# attiny13ReobasNew_2021-02-27.net
KiCad netlist of a schematic drawn in EasyEDA
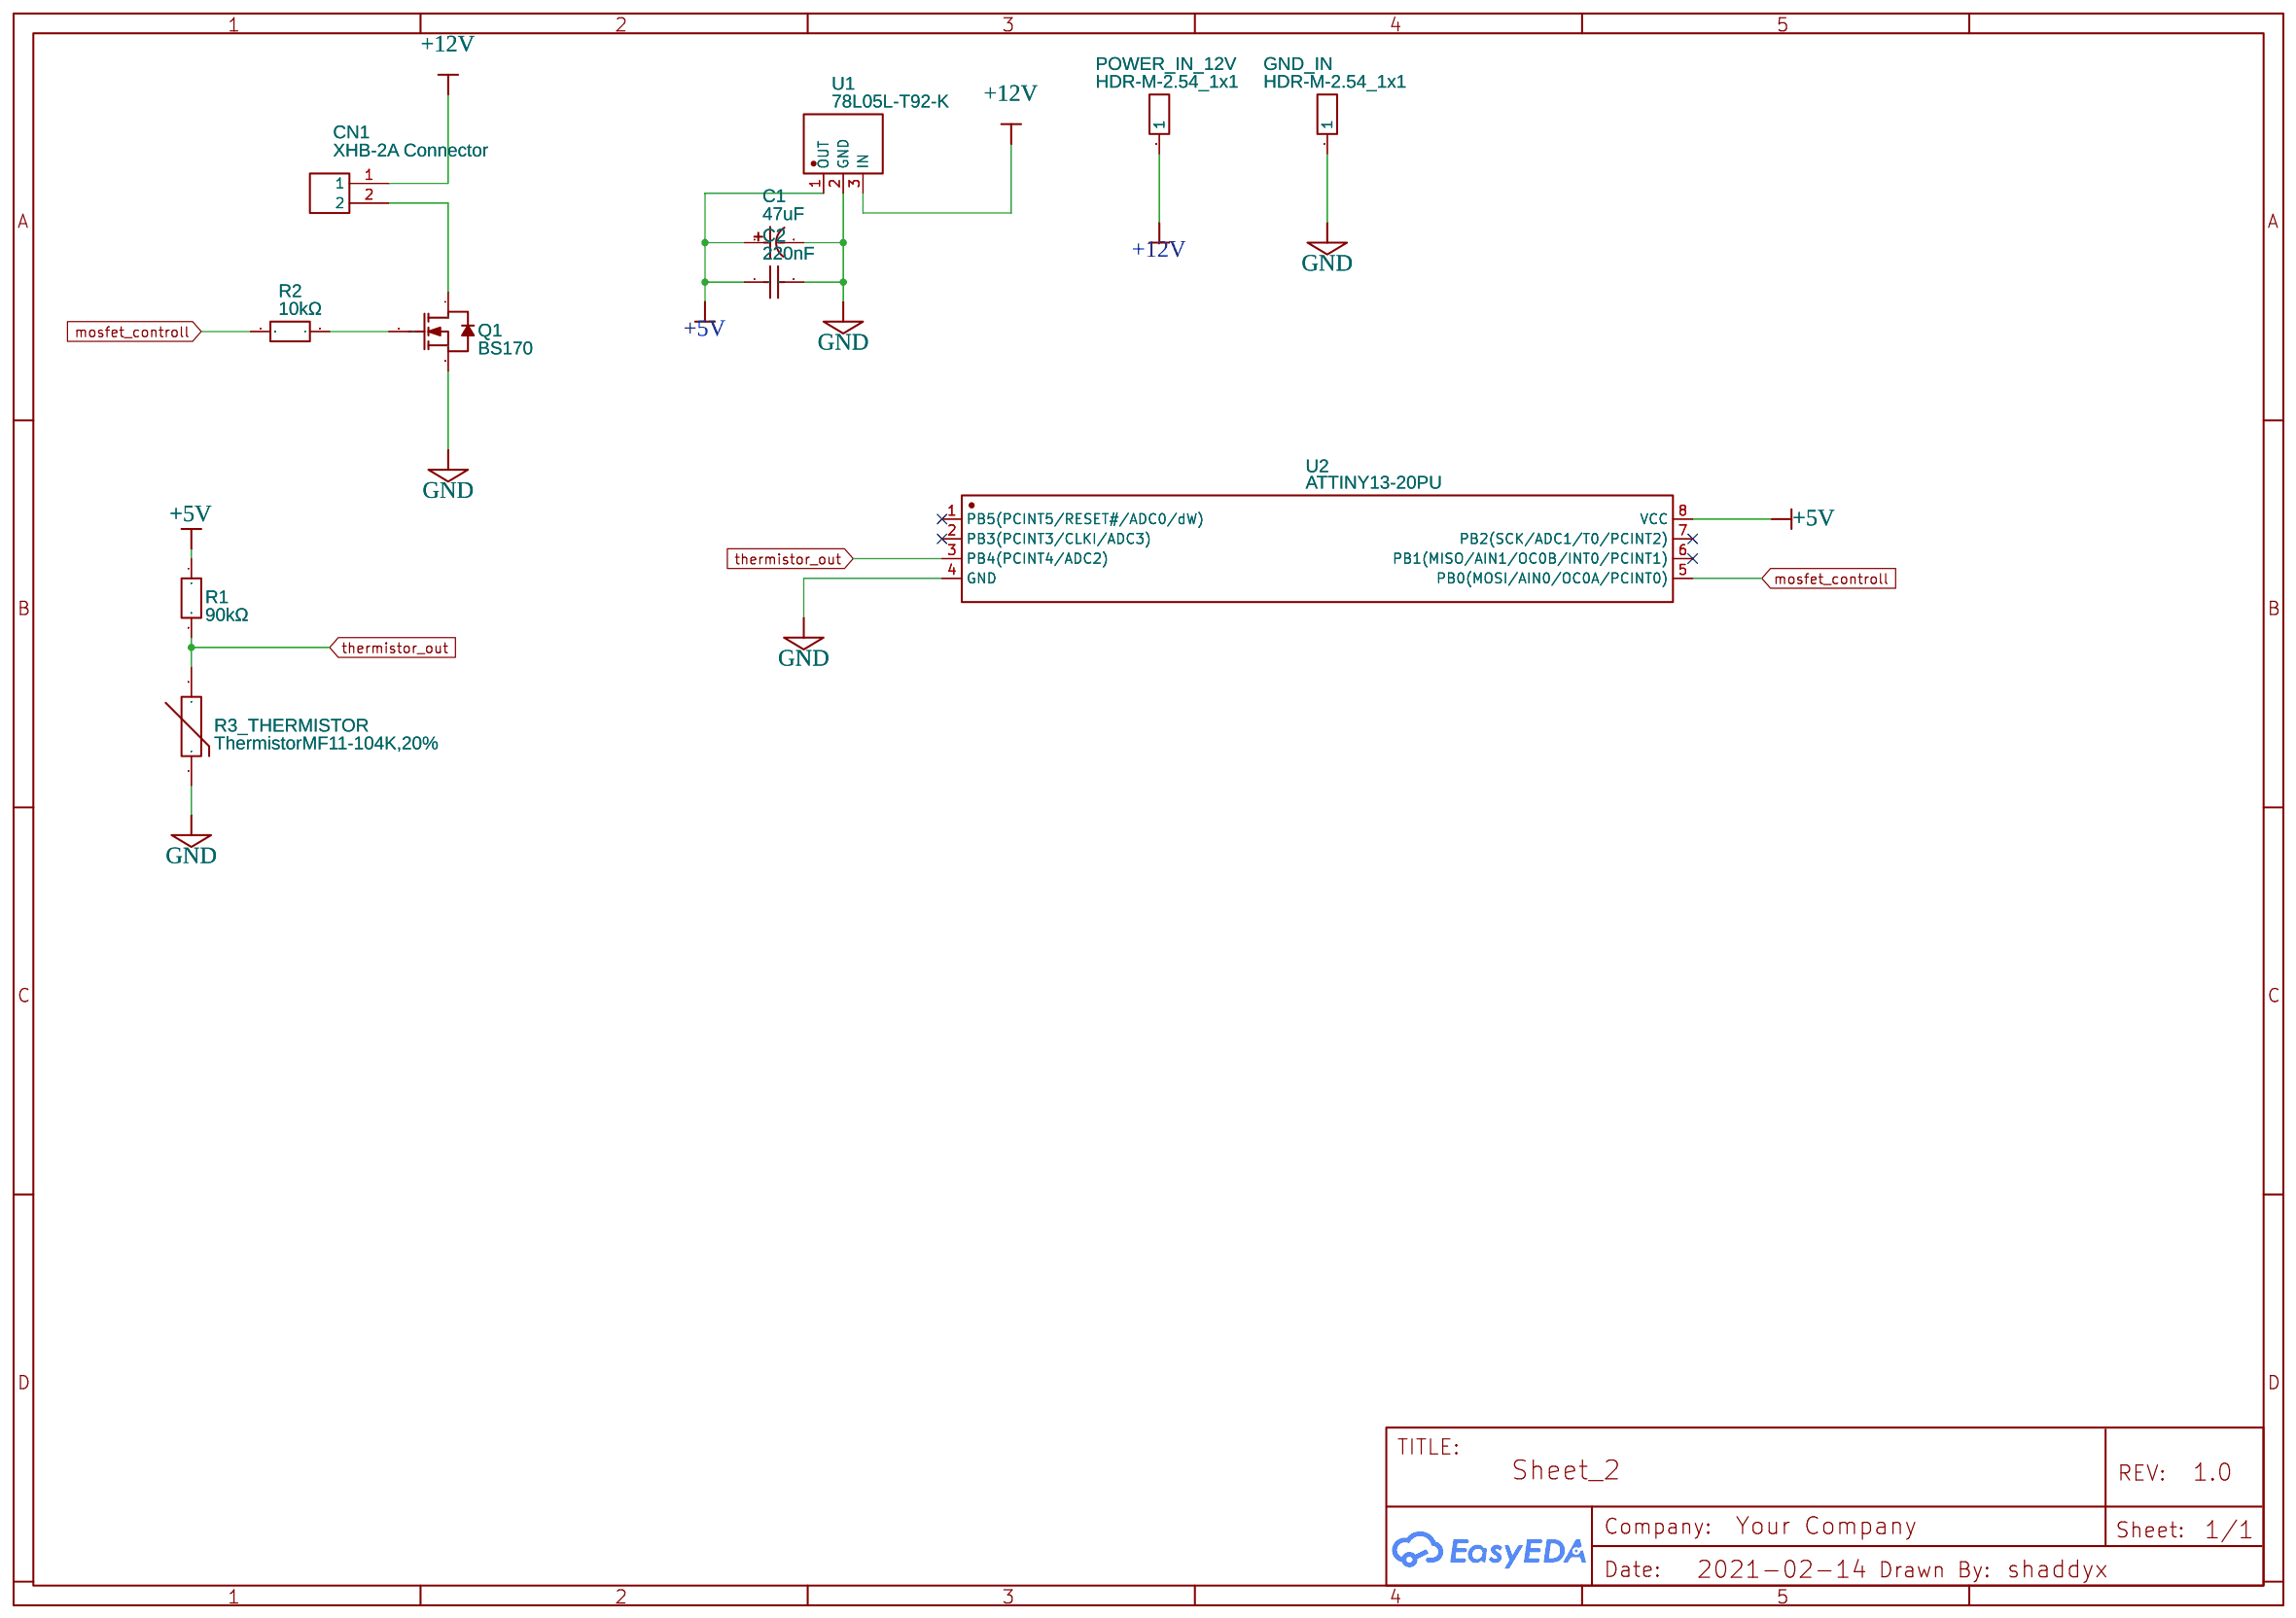
[diagram p0: schematic sheet]

(export (version "E")
  (design (tool "Eeschema 10.0.6"))
  (components
    (comp (ref "C1")
      (value "47uF")
      (fields
        (field (name "BOM_Manufacturer Part") "electrolytic capacitor10UF50V")
        (field (name "BOM_Supplier Part") "C32856")
      )
      (libsource (lib "") (part "electrolytic capacitor10UF50V"))
    )
    (comp (ref "C2")
      (value "220nF")
      (fields
        (field (name "BOM_Manufacturer Part") "CT4-0805Y224 M500")
        (field (name "BOM_Supplier Part") "C3786")
      )
      (libsource (lib "") (part "CT4-0805Y224 M500"))
    )
    (comp (ref "CN1")
      (value "XHB-2A Connector")
      (fields (field (name "BOM_Supplier Part") "C57981"))
      (libsource (lib "") (part "XHB-2A Connector"))
    )
    (comp (ref "GND_IN")
      (value "HDR-M-2.54_1x1")
      (fields (field (name "BOM_Supplier Part") "C81276"))
      (libsource (lib "") (part "HDR-M-2.54_1x1_1"))
    )
    (comp (ref "POWER_IN_12V")
      (value "HDR-M-2.54_1x1")
      (fields (field (name "BOM_Supplier Part") "C81276"))
      (libsource (lib "") (part "HDR-M-2.54_1x1"))
    )
    (comp (ref "Q1")
      (value "BS170")
      (fields (field (name "BOM_Supplier Part") "C111691"))
      (libsource (lib "") (part "BS170"))
    )
    (comp (ref "R1")
      (value "90kΩ")
      (fields
        (field (name "BOM_Manufacturer Part") "CF1/6W-18KΩ±5%T52")
        (field (name "BOM_Supplier Part") "C714235")
      )
      (libsource (lib "") (part "CF1/6W-18KΩ±5%T52"))
    )
    (comp (ref "R2")
      (value "10kΩ")
      (fields
        (field (name "BOM_Manufacturer Part") "CF1/6W-18KΩ±5%T52")
        (field (name "BOM_Supplier Part") "C714235")
      )
      (libsource (lib "") (part "CF1/6W-18KΩ±5%T52_1"))
    )
    (comp (ref "R3_THERMISTOR")
      (value "ThermistorMF11-104K,20%")
      (fields (field (name "BOM_Manufacturer Part") "MF11-104K") (field (name "BOM_Supplier Part") "C40773"))
      (libsource (lib "") (part "MF11-104K"))
    )
    (comp (ref "U1")
      (value "78L05L-T92-K")
      (fields (field (name "BOM_Supplier Part") "C380213"))
      (libsource (lib "") (part "78L05L-T92-K"))
    )
    (comp (ref "U2")
      (value "ATTINY13-20PU")
      (fields (field (name "BOM_Supplier Part") "C145757"))
      (libsource (lib "") (part "ATTINY13-20PU"))
    )
  )
  (nets
    (net (code "1") (name "+5V") (class "Default")
      (node (ref "C1") (pin "1") (pinfunction "+_1") (pintype "input"))
      (node (ref "C2") (pin "1") (pinfunction "1_1") (pintype "input"))
      (node (ref "R1") (pin "1") (pinfunction "1_1") (pintype "unspecified"))
      (node (ref "U1") (pin "1") (pinfunction "OUT_1") (pintype "unspecified"))
      (node (ref "U2") (pin "8") (pinfunction "VCC_8") (pintype "unspecified"))
    )
    (net (code "2") (name "+12V") (class "Default")
      (node (ref "CN1") (pin "1") (pinfunction "1_1") (pintype "unspecified"))
      (node (ref "POWER_IN_12V") (pin "1") (pinfunction "1_1") (pintype "input"))
      (node (ref "U1") (pin "3") (pinfunction "IN_3") (pintype "unspecified"))
    )
    (net (code "3") (name "GND") (class "Default")
      (node (ref "C1") (pin "2") (pinfunction "-_2") (pintype "input"))
      (node (ref "C2") (pin "2") (pinfunction "2_2") (pintype "input"))
      (node (ref "GND_IN") (pin "1") (pinfunction "1_1") (pintype "input"))
      (node (ref "Q1") (pin "3") (pinfunction "S_3") (pintype "unspecified"))
      (node (ref "R3_THERMISTOR") (pin "1") (pinfunction "1_1") (pintype "unspecified"))
      (node (ref "U1") (pin "2") (pinfunction "GND_2") (pintype "unspecified"))
      (node (ref "U2") (pin "4") (pinfunction "GND_4") (pintype "unspecified"))
    )
    (net (code "4") (name "Net-(Q1-D)") (class "Default")
      (node (ref "CN1") (pin "2") (pinfunction "2_2") (pintype "unspecified"))
      (node (ref "Q1") (pin "1") (pinfunction "D_1") (pintype "unspecified"))
    )
    (net (code "5") (name "Net-(Q1-G)") (class "Default")
      (node (ref "Q1") (pin "2") (pinfunction "G_2") (pintype "unspecified"))
      (node (ref "R2") (pin "1") (pinfunction "1_1") (pintype "unspecified"))
    )
    (net (code "6") (name "mosfet_controll") (class "Default")
      (node (ref "R2") (pin "2") (pinfunction "2_2") (pintype "unspecified"))
      (node (ref "U2") (pin "5") (pinfunction "PB0(MOSI/AIN0/OC0A/PCINT0)_5") (pintype "unspecified"))
    )
    (net (code "7") (name "thermistor_out") (class "Default")
      (node (ref "R1") (pin "2") (pinfunction "2_2") (pintype "unspecified"))
      (node (ref "R3_THERMISTOR") (pin "2") (pinfunction "2_2") (pintype "unspecified"))
      (node (ref "U2") (pin "3") (pinfunction "PB4(PCINT4/ADC2)_3") (pintype "unspecified"))
    )
    (net (code "8") (name "unconnected-(U2-PB1(MISO{slash}AIN1{slash}OC0B{slash}INT0{slash}PCINT1)-Pad6)") (class "Default")
      (node (ref "U2") (pin "6") (pinfunction "PB1(MISO/AIN1/OC0B/INT0/PCINT1)_6") (pintype "unspecified+no_connect"))
    )
    (net (code "9") (name "unconnected-(U2-PB2(SCK{slash}ADC1{slash}T0{slash}PCINT2)-Pad7)") (class "Default")
      (node (ref "U2") (pin "7") (pinfunction "PB2(SCK/ADC1/T0/PCINT2)_7") (pintype "unspecified+no_connect"))
    )
    (net (code "10") (name "unconnected-(U2-PB3(PCINT3{slash}CLKI{slash}ADC3)-Pad2)") (class "Default")
      (node (ref "U2") (pin "2") (pinfunction "PB3(PCINT3/CLKI/ADC3)_2") (pintype "unspecified+no_connect"))
    )
    (net (code "11") (name "unconnected-(U2-PB5(PCINT5{slash}RESET#{slash}ADC0{slash}dW)-Pad1)") (class "Default")
      (node (ref "U2") (pin "1") (pinfunction "PB5(PCINT5/RESET#/ADC0/dW)_1") (pintype "unspecified+no_connect"))
    )
  )
)
